# button.net
KiCad netlist of a schematic drawn in Altium Designer
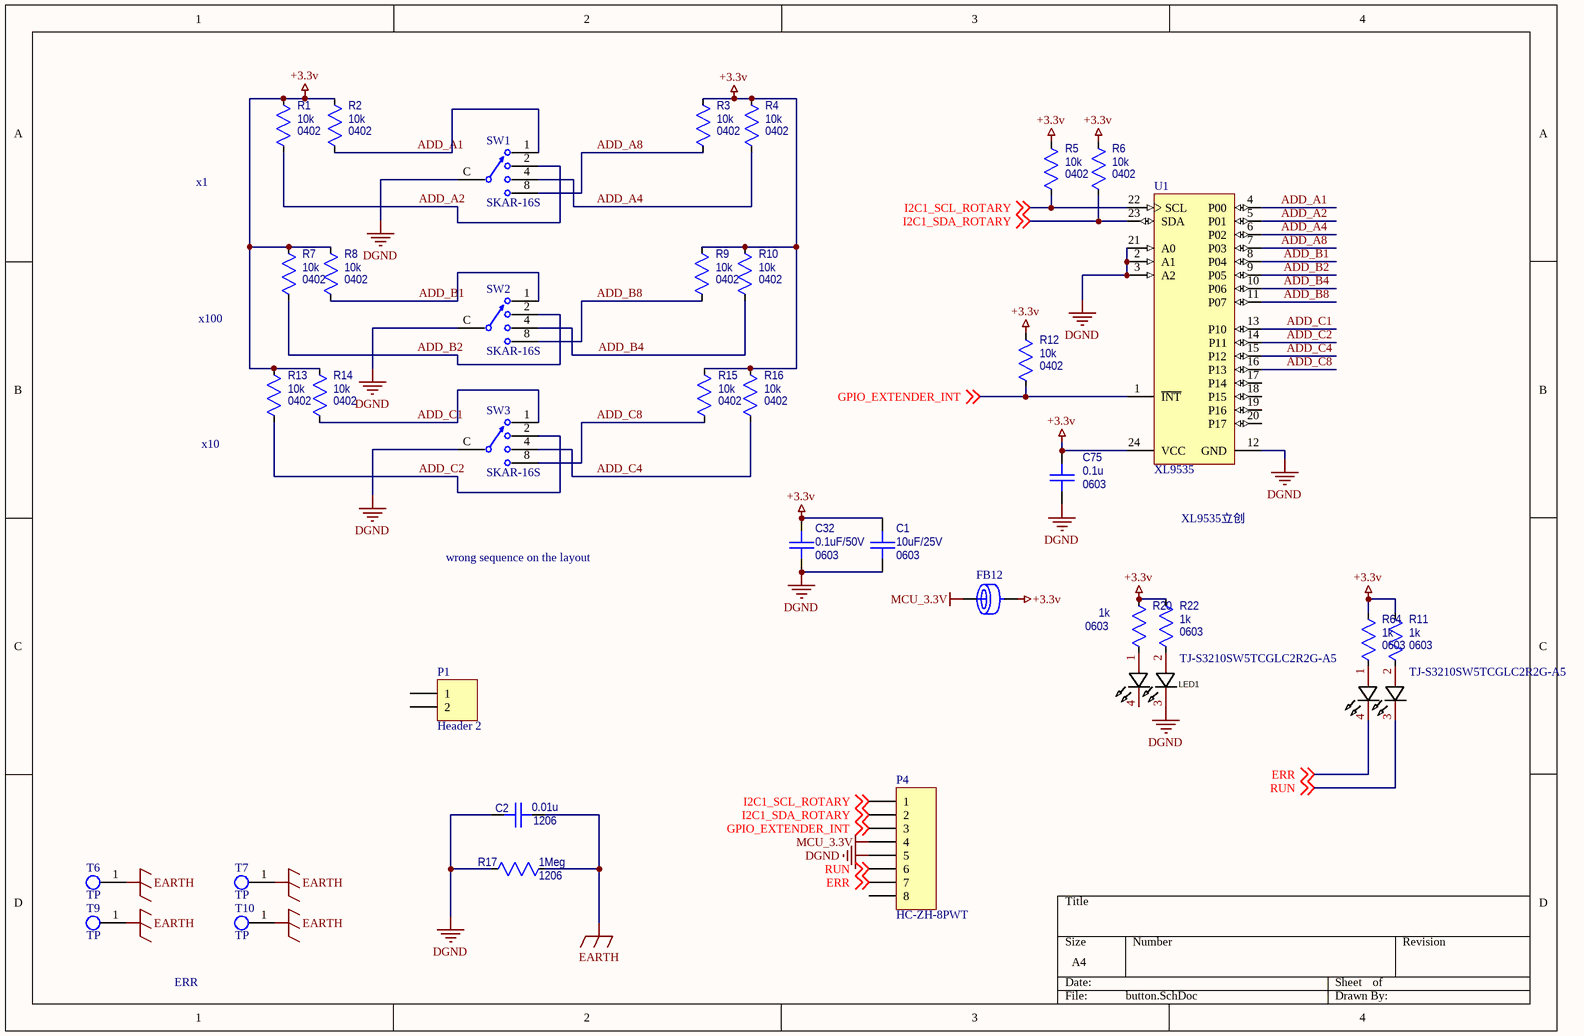
[diagram p0: button.SchDoc]

(export (version "E")
  (design (tool "Eeschema 10.0.6"))
  (components
    (comp (ref "C1")
      (value "10uF/25V")
      (footprint "CAPC1608X092N_0603")
      (fields
        (field (name "PARTNUMBER") "C0603C104M5RACTU")
        (field (name "TOLERANCE") "[tol]")
        (field (name "PACKAGE") "0603")
        (field (name "Comment") "Capacitor_0603")
      )
      (libsource (lib "Karl") (part "Capacitor_0603"))
    )
    (comp (ref "C2")
      (value "0.01u")
      (footprint "CAPC3216X156N_1206")
      (description "Capacitor, MLCC")
      (fields
        (field (name "PARTNUMBER") "C1206C103KCRACTU")
        (field (name "TOLERANCE") "[tol]")
        (field (name "PACKAGE") "1206")
      )
      (libsource (lib "Karl") (part "Capacitor_1206"))
    )
    (comp (ref "C32")
      (value "0.1uF/50V")
      (footprint "CAPC1608X092N_0603")
      (fields
        (field (name "PARTNUMBER") "C0603C104M5RACTU")
        (field (name "TOLERANCE") "[tol]")
        (field (name "PACKAGE") "0603")
        (field (name "Comment") "Capacitor_0603")
      )
      (libsource (lib "Karl") (part "Capacitor_0603"))
    )
    (comp (ref "C75")
      (value "0.1u")
      (footprint "CAPC1608X092N_0603")
      (description "Capacitor, MLCC")
      (fields
        (field (name "MANUFACTURER") "KEMET")
        (field (name "PARTNUMBER") "C0603C104M5RACTU")
        (field (name "PACKAGE") "0603")
      )
      (libsource (lib "Karl") (part "Capacitor_0603"))
    )
    (comp (ref "FB12")
      (value "FBC0603")
      (footprint "FBC0603")
      (fields (field (name "PARTNUMBER") "PE-0603PFB121ST"))
      (libsource (lib "Karl") (part "FBC0603"))
    )
    (comp (ref "LED1")
      (value "TJ-S3210SW5TCGLC2R2G-A5")
      (footprint "LED-SMD_4P-L3.2-W1.5_TJ-S3210SW5TCGLC2R2G")
      (libsource (lib "altium-import") (part "root_1_TJ-S3210SW5TCGLC2R2G-A5_"))
    )
    (comp (ref "LED2")
      (value "TJ-S3210SW5TCGLC2R2G-A5")
      (footprint "LED-SMD_4P-L3.2-W1.5_TJ-S3210SW5TCGLC2R2G")
      (libsource (lib "altium-import") (part "root_1_TJ-S3210SW5TCGLC2R2G-A5_"))
    )
    (comp (ref "P1")
      (value "Header 2")
      (footprint "HDR1X2")
      (description "Header, 2-Pin")
      (fields (field (name "PUBLISHER") "Altium Limited"))
      (libsource (lib "Miscellaneous Connectors") (part "Header 2"))
    )
    (comp (ref "P4")
      (value "HC-ZH-8PWT")
      (footprint "CONN-TH_HC-ZH1.5-8A")
      (description "Header, 8-Pin")
      (fields (field (name "PUBLISHER") "Altium Limited"))
      (libsource (lib "Miscellaneous Connectors") (part "Header 8"))
    )
    (comp (ref "R1")
      (value "10k")
      (footprint "RESC1608X055N_0603")
      (description "Resistor, Standard")
      (fields
        (field (name "MANUFACTURER") "Panasonic")
        (field (name "PARTNUMBER") "ERJ-2RKF1002X")
        (field (name "PACKAGE") "0402")
      )
      (libsource (lib "Karl") (part "Resistor_0402"))
    )
    (comp (ref "R2")
      (value "10k")
      (footprint "RESC1608X055N_0603")
      (description "Resistor, Standard")
      (fields
        (field (name "MANUFACTURER") "Panasonic")
        (field (name "PARTNUMBER") "ERJ-2RKF1002X")
        (field (name "PACKAGE") "0402")
      )
      (libsource (lib "Karl") (part "Resistor_0402"))
    )
    (comp (ref "R3")
      (value "10k")
      (footprint "RESC1608X055N_0603")
      (description "Resistor, Standard")
      (fields
        (field (name "MANUFACTURER") "Panasonic")
        (field (name "PARTNUMBER") "ERJ-2RKF1002X")
        (field (name "PACKAGE") "0402")
      )
      (libsource (lib "Karl") (part "Resistor_0402"))
    )
    (comp (ref "R4")
      (value "10k")
      (footprint "RESC1608X055N_0603")
      (description "Resistor, Standard")
      (fields
        (field (name "MANUFACTURER") "Panasonic")
        (field (name "PARTNUMBER") "ERJ-2RKF1002X")
        (field (name "PACKAGE") "0402")
      )
      (libsource (lib "Karl") (part "Resistor_0402"))
    )
    (comp (ref "R5")
      (value "10k")
      (footprint "RESC1608X055N_0603")
      (description "Resistor, Standard")
      (fields
        (field (name "MANUFACTURER") "Panasonic")
        (field (name "PARTNUMBER") "ERJ-2RKF1002X")
        (field (name "PACKAGE") "0402")
      )
      (libsource (lib "Karl") (part "Resistor_0402"))
    )
    (comp (ref "R6")
      (value "10k")
      (footprint "RESC1608X055N_0603")
      (description "Resistor, Standard")
      (fields
        (field (name "MANUFACTURER") "Panasonic")
        (field (name "PARTNUMBER") "ERJ-2RKF1002X")
        (field (name "PACKAGE") "0402")
      )
      (libsource (lib "Karl") (part "Resistor_0402"))
    )
    (comp (ref "R7")
      (value "10k")
      (footprint "RESC1608X055N_0603")
      (description "Resistor, Standard")
      (fields
        (field (name "MANUFACTURER") "Panasonic")
        (field (name "PARTNUMBER") "ERJ-2RKF1002X")
        (field (name "PACKAGE") "0402")
      )
      (libsource (lib "Karl") (part "Resistor_0402"))
    )
    (comp (ref "R8")
      (value "10k")
      (footprint "RESC1608X055N_0603")
      (description "Resistor, Standard")
      (fields
        (field (name "MANUFACTURER") "Panasonic")
        (field (name "PARTNUMBER") "ERJ-2RKF1002X")
        (field (name "PACKAGE") "0402")
      )
      (libsource (lib "Karl") (part "Resistor_0402"))
    )
    (comp (ref "R9")
      (value "10k")
      (footprint "RESC1608X055N_0603")
      (description "Resistor, Standard")
      (fields
        (field (name "MANUFACTURER") "Panasonic")
        (field (name "PARTNUMBER") "ERJ-2RKF1002X")
        (field (name "PACKAGE") "0402")
      )
      (libsource (lib "Karl") (part "Resistor_0402"))
    )
    (comp (ref "R10")
      (value "10k")
      (footprint "RESC1608X055N_0603")
      (description "Resistor, Standard")
      (fields
        (field (name "MANUFACTURER") "Panasonic")
        (field (name "PARTNUMBER") "ERJ-2RKF1002X")
        (field (name "PACKAGE") "0402")
      )
      (libsource (lib "Karl") (part "Resistor_0402"))
    )
    (comp (ref "R11")
      (value "1k")
      (footprint "RESC1608X055N_0603")
      (description "Resistor, Standard")
      (fields
        (field (name "MANUFACTURER") "Yageo")
        (field (name "PARTNUMBER") "RC0603FR-071KL")
        (field (name "PACKAGE") "0603")
      )
      (libsource (lib "Karl") (part "Resistor_0603"))
    )
    (comp (ref "R12")
      (value "10k")
      (footprint "RESC1608X055N_0603")
      (description "Resistor, Standard")
      (fields
        (field (name "MANUFACTURER") "Panasonic")
        (field (name "PARTNUMBER") "ERJ-2RKF1002X")
        (field (name "PACKAGE") "0402")
      )
      (libsource (lib "Karl") (part "Resistor_0402"))
    )
    (comp (ref "R13")
      (value "10k")
      (footprint "RESC1608X055N_0603")
      (description "Resistor, Standard")
      (fields
        (field (name "MANUFACTURER") "Panasonic")
        (field (name "PARTNUMBER") "ERJ-2RKF1002X")
        (field (name "PACKAGE") "0402")
      )
      (libsource (lib "Karl") (part "Resistor_0402"))
    )
    (comp (ref "R14")
      (value "10k")
      (footprint "RESC1608X055N_0603")
      (description "Resistor, Standard")
      (fields
        (field (name "MANUFACTURER") "Panasonic")
        (field (name "PARTNUMBER") "ERJ-2RKF1002X")
        (field (name "PACKAGE") "0402")
      )
      (libsource (lib "Karl") (part "Resistor_0402"))
    )
    (comp (ref "R15")
      (value "10k")
      (footprint "RESC1608X055N_0603")
      (description "Resistor, Standard")
      (fields
        (field (name "MANUFACTURER") "Panasonic")
        (field (name "PARTNUMBER") "ERJ-2RKF1002X")
        (field (name "PACKAGE") "0402")
      )
      (libsource (lib "Karl") (part "Resistor_0402"))
    )
    (comp (ref "R16")
      (value "10k")
      (footprint "RESC1608X055N_0603")
      (description "Resistor, Standard")
      (fields
        (field (name "MANUFACTURER") "Panasonic")
        (field (name "PARTNUMBER") "ERJ-2RKF1002X")
        (field (name "PACKAGE") "0402")
      )
      (libsource (lib "Karl") (part "Resistor_0402"))
    )
    (comp (ref "R17")
      (value "1Meg")
      (footprint "RESC3216X070N_1206")
      (description "Resistor, Standard")
      (fields
        (field (name "PARTNUMBER") "RC1206FR-071ML")
        (field (name "TOLERANCE") "tol")
        (field (name "PACKAGE") "1206")
      )
      (libsource (lib "Karl") (part "Resistor_1206"))
    )
    (comp (ref "R20")
      (value "1k")
      (footprint "RESC1608X055N_0603")
      (description "Resistor, Standard")
      (fields
        (field (name "MANUFACTURER") "Yageo")
        (field (name "PARTNUMBER") "RC0603FR-071KL")
        (field (name "PACKAGE") "0603")
      )
      (libsource (lib "Karl") (part "Resistor_0603"))
    )
    (comp (ref "R22")
      (value "1k")
      (footprint "RESC1608X055N_0603")
      (description "Resistor, Standard")
      (fields
        (field (name "MANUFACTURER") "Yageo")
        (field (name "PARTNUMBER") "RC0603FR-071KL")
        (field (name "PACKAGE") "0603")
      )
      (libsource (lib "Karl") (part "Resistor_0603"))
    )
    (comp (ref "R64")
      (value "1k")
      (footprint "RESC1608X055N_0603")
      (description "Resistor, Standard")
      (fields
        (field (name "MANUFACTURER") "Yageo")
        (field (name "PARTNUMBER") "RC0603FR-071KL")
        (field (name "PACKAGE") "0603")
      )
      (libsource (lib "Karl") (part "Resistor_0603"))
    )
    (comp (ref "SW1")
      (value "SKAR-16S")
      (footprint "SW-SMD_SM_STAR-10S")
      (description "Mini Rotary DIP Switch, 16 Postions, Right Angle Thru-Hole, -60 to 125 degC, 6-Pin THT, RoHS")
      (fields (field (name "PART NO") "MSDR-16H1") (field (name "MANUFACTURER") "SUNGMUN ELECTRONICS"))
      (libsource (lib "Bogen") (part "MSDR-16H1"))
    )
    (comp (ref "SW2")
      (value "SKAR-16S")
      (footprint "SW-SMD_SM_STAR-10S")
      (description "Mini Rotary DIP Switch, 16 Postions, Right Angle Thru-Hole, -60 to 125 degC, 6-Pin THT, RoHS")
      (fields (field (name "PART NO") "MSDR-16H1") (field (name "MANUFACTURER") "SUNGMUN ELECTRONICS"))
      (libsource (lib "Bogen") (part "MSDR-16H1"))
    )
    (comp (ref "SW3")
      (value "SKAR-16S")
      (footprint "SW-SMD_SM_STAR-10S")
      (description "Mini Rotary DIP Switch, 16 Postions, Right Angle Thru-Hole, -60 to 125 degC, 6-Pin THT, RoHS")
      (fields (field (name "PART NO") "MSDR-16H1") (field (name "MANUFACTURER") "SUNGMUN ELECTRONICS"))
      (libsource (lib "Bogen") (part "MSDR-16H1"))
    )
    (comp (ref "T6") (value "TP") (footprint "FIX-2.5") (libsource (lib "Schlib_20110825") (part "TP")))
    (comp (ref "T7") (value "TP") (footprint "FIX-2.5") (libsource (lib "Schlib_20110825") (part "TP")))
    (comp (ref "T9") (value "TP") (footprint "FIX-2.5") (libsource (lib "Schlib_20110825") (part "TP")))
    (comp (ref "T10") (value "TP") (footprint "FIX-2.5") (libsource (lib "Schlib_20110825") (part "TP")))
    (comp (ref "U1")
      (value "XL9535")
      (footprint "XNLD-TSSOP24_N")
      (fields (field (name "MANUFACTURER") "XINLUDA"))
      (libsource (lib "Bogen") (part "XL9535"))
    )
  )
  (nets
    (net (code "1") (name "+3.3v") (class "Default")
      (node (ref "C1") (pin "1") (pinfunction "1_1") (pintype "passive"))
      (node (ref "C32") (pin "1") (pinfunction "1_1") (pintype "passive"))
      (node (ref "C75") (pin "1") (pinfunction "1_1") (pintype "passive"))
      (node (ref "FB12") (pin "2") (pinfunction "2_2") (pintype "passive"))
      (node (ref "R1") (pin "2") (pinfunction "2_2") (pintype "passive"))
      (node (ref "R10") (pin "2") (pinfunction "2_2") (pintype "passive"))
      (node (ref "R11") (pin "2") (pinfunction "2_2") (pintype "passive"))
      (node (ref "R12") (pin "2") (pinfunction "2_2") (pintype "passive"))
      (node (ref "R13") (pin "2") (pinfunction "2_2") (pintype "passive"))
      (node (ref "R14") (pin "2") (pinfunction "2_2") (pintype "passive"))
      (node (ref "R15") (pin "2") (pinfunction "2_2") (pintype "passive"))
      (node (ref "R16") (pin "2") (pinfunction "2_2") (pintype "passive"))
      (node (ref "R2") (pin "2") (pinfunction "2_2") (pintype "passive"))
      (node (ref "R20") (pin "2") (pinfunction "2_2") (pintype "passive"))
      (node (ref "R22") (pin "2") (pinfunction "2_2") (pintype "passive"))
      (node (ref "R3") (pin "2") (pinfunction "2_2") (pintype "passive"))
      (node (ref "R4") (pin "2") (pinfunction "2_2") (pintype "passive"))
      (node (ref "R5") (pin "2") (pinfunction "2_2") (pintype "passive"))
      (node (ref "R6") (pin "2") (pinfunction "2_2") (pintype "passive"))
      (node (ref "R64") (pin "2") (pinfunction "2_2") (pintype "passive"))
      (node (ref "R7") (pin "2") (pinfunction "2_2") (pintype "passive"))
      (node (ref "R8") (pin "2") (pinfunction "2_2") (pintype "passive"))
      (node (ref "R9") (pin "2") (pinfunction "2_2") (pintype "passive"))
      (node (ref "U1") (pin "24") (pinfunction "VCC_24") (pintype "power_in"))
    )
    (net (code "2") (name "/ADD_A1") (class "Default")
      (node (ref "R2") (pin "1") (pinfunction "1_1") (pintype "passive"))
      (node (ref "SW1") (pin "1") (pinfunction "1_1") (pintype "passive"))
      (node (ref "U1") (pin "4") (pinfunction "P00_4") (pintype "bidirectional"))
    )
    (net (code "3") (name "/ADD_A2") (class "Default")
      (node (ref "R1") (pin "1") (pinfunction "1_1") (pintype "passive"))
      (node (ref "SW1") (pin "2") (pinfunction "2_2") (pintype "passive"))
      (node (ref "U1") (pin "5") (pinfunction "P01_5") (pintype "bidirectional"))
    )
    (net (code "4") (name "/ADD_A4") (class "Default")
      (node (ref "R4") (pin "1") (pinfunction "1_1") (pintype "passive"))
      (node (ref "SW1") (pin "4") (pinfunction "4_4") (pintype "passive"))
      (node (ref "U1") (pin "6") (pinfunction "P02_6") (pintype "bidirectional"))
    )
    (net (code "5") (name "/ADD_A8") (class "Default")
      (node (ref "R3") (pin "1") (pinfunction "1_1") (pintype "passive"))
      (node (ref "SW1") (pin "8") (pinfunction "8_8") (pintype "passive"))
      (node (ref "U1") (pin "7") (pinfunction "P03_7") (pintype "bidirectional"))
    )
    (net (code "6") (name "/ADD_B1") (class "Default")
      (node (ref "R8") (pin "1") (pinfunction "1_1") (pintype "passive"))
      (node (ref "SW2") (pin "1") (pinfunction "1_1") (pintype "passive"))
      (node (ref "U1") (pin "8") (pinfunction "P04_8") (pintype "bidirectional"))
    )
    (net (code "7") (name "/ADD_B2") (class "Default")
      (node (ref "R7") (pin "1") (pinfunction "1_1") (pintype "passive"))
      (node (ref "SW2") (pin "2") (pinfunction "2_2") (pintype "passive"))
      (node (ref "U1") (pin "9") (pinfunction "P05_9") (pintype "bidirectional"))
    )
    (net (code "8") (name "/ADD_B4") (class "Default")
      (node (ref "R10") (pin "1") (pinfunction "1_1") (pintype "passive"))
      (node (ref "SW2") (pin "4") (pinfunction "4_4") (pintype "passive"))
      (node (ref "U1") (pin "10") (pinfunction "P06_10") (pintype "bidirectional"))
    )
    (net (code "9") (name "/ADD_B8") (class "Default")
      (node (ref "R9") (pin "1") (pinfunction "1_1") (pintype "passive"))
      (node (ref "SW2") (pin "8") (pinfunction "8_8") (pintype "passive"))
      (node (ref "U1") (pin "11") (pinfunction "P07_11") (pintype "bidirectional"))
    )
    (net (code "10") (name "/ADD_C1") (class "Default")
      (node (ref "R14") (pin "1") (pinfunction "1_1") (pintype "passive"))
      (node (ref "SW3") (pin "1") (pinfunction "1_1") (pintype "passive"))
      (node (ref "U1") (pin "13") (pinfunction "P10_13") (pintype "bidirectional"))
    )
    (net (code "11") (name "/ADD_C2") (class "Default")
      (node (ref "R13") (pin "1") (pinfunction "1_1") (pintype "passive"))
      (node (ref "SW3") (pin "2") (pinfunction "2_2") (pintype "passive"))
      (node (ref "U1") (pin "14") (pinfunction "P11_14") (pintype "bidirectional"))
    )
    (net (code "12") (name "/ADD_C4") (class "Default")
      (node (ref "R16") (pin "1") (pinfunction "1_1") (pintype "passive"))
      (node (ref "SW3") (pin "4") (pinfunction "4_4") (pintype "passive"))
      (node (ref "U1") (pin "15") (pinfunction "P12_15") (pintype "bidirectional"))
    )
    (net (code "13") (name "/ADD_C8") (class "Default")
      (node (ref "R15") (pin "1") (pinfunction "1_1") (pintype "passive"))
      (node (ref "SW3") (pin "8") (pinfunction "8_8") (pintype "passive"))
      (node (ref "U1") (pin "16") (pinfunction "P13_16") (pintype "bidirectional"))
    )
    (net (code "14") (name "DGND") (class "Default")
      (node (ref "C1") (pin "2") (pinfunction "2_2") (pintype "passive"))
      (node (ref "C2") (pin "1") (pinfunction "1_1") (pintype "passive"))
      (node (ref "C32") (pin "2") (pinfunction "2_2") (pintype "passive"))
      (node (ref "C75") (pin "2") (pinfunction "2_2") (pintype "passive"))
      (node (ref "LED1") (pin "3") (pinfunction "-_3") (pintype "passive"))
      (node (ref "P4") (pin "5") (pinfunction "5_5") (pintype "passive"))
      (node (ref "R17") (pin "2") (pinfunction "2_2") (pintype "passive"))
      (node (ref "SW1") (pin "C") (pinfunction "C_C") (pintype "passive"))
      (node (ref "SW2") (pin "C") (pinfunction "C_C") (pintype "passive"))
      (node (ref "SW3") (pin "C") (pinfunction "C_C") (pintype "passive"))
      (node (ref "U1") (pin "12") (pinfunction "GND_12") (pintype "power_in"))
      (node (ref "U1") (pin "2") (pinfunction "A1_2") (pintype "input"))
      (node (ref "U1") (pin "21") (pinfunction "A0_21") (pintype "input"))
      (node (ref "U1") (pin "3") (pinfunction "A2_3") (pintype "input"))
    )
    (net (code "15") (name "EARTH") (class "Default")
      (node (ref "C2") (pin "2") (pinfunction "2_2") (pintype "passive"))
      (node (ref "R17") (pin "1") (pinfunction "1_1") (pintype "passive"))
      (node (ref "T10") (pin "1") (pintype "passive"))
      (node (ref "T6") (pin "1") (pintype "passive"))
      (node (ref "T7") (pin "1") (pintype "passive"))
      (node (ref "T9") (pin "1") (pintype "passive"))
    )
    (net (code "16") (name "ERR") (class "Default")
      (node (ref "LED2") (pin "4") (pinfunction "-_4") (pintype "passive"))
      (node (ref "P4") (pin "7") (pinfunction "7_7") (pintype "passive"))
    )
    (net (code "17") (name "GPIO_EXTENDER_INT") (class "Default")
      (node (ref "P4") (pin "3") (pinfunction "3_3") (pintype "passive"))
      (node (ref "R12") (pin "1") (pinfunction "1_1") (pintype "passive"))
      (node (ref "U1") (pin "1") (pinfunction "~{INT}_1") (pintype "open_collector"))
    )
    (net (code "18") (name "I2C1_SCL_ROTARY") (class "Default")
      (node (ref "P4") (pin "1") (pinfunction "1_1") (pintype "passive"))
      (node (ref "R5") (pin "1") (pinfunction "1_1") (pintype "passive"))
      (node (ref "U1") (pin "22") (pinfunction "SCL_22") (pintype "input"))
    )
    (net (code "19") (name "I2C1_SDA_ROTARY") (class "Default")
      (node (ref "P4") (pin "2") (pinfunction "2_2") (pintype "passive"))
      (node (ref "R6") (pin "1") (pinfunction "1_1") (pintype "passive"))
      (node (ref "U1") (pin "23") (pinfunction "SDA_23") (pintype "bidirectional"))
    )
    (net (code "20") (name "MCU_3.3V") (class "Default")
      (node (ref "FB12") (pin "1") (pinfunction "1_1") (pintype "passive"))
      (node (ref "P4") (pin "4") (pinfunction "4_4") (pintype "passive"))
    )
    (net (code "21") (name "Net-(LED1-+-Pad1)") (class "Default")
      (node (ref "LED1") (pin "1") (pinfunction "+_1") (pintype "passive"))
      (node (ref "R20") (pin "1") (pinfunction "1_1") (pintype "passive"))
    )
    (net (code "22") (name "Net-(LED1-+-Pad2)") (class "Default")
      (node (ref "LED1") (pin "2") (pinfunction "+_2") (pintype "passive"))
      (node (ref "R22") (pin "1") (pinfunction "1_1") (pintype "passive"))
    )
    (net (code "23") (name "Net-(LED2-+-Pad1)") (class "Default")
      (node (ref "LED2") (pin "1") (pinfunction "+_1") (pintype "passive"))
      (node (ref "R64") (pin "1") (pinfunction "1_1") (pintype "passive"))
    )
    (net (code "24") (name "Net-(LED2-+-Pad2)") (class "Default")
      (node (ref "LED2") (pin "2") (pinfunction "+_2") (pintype "passive"))
      (node (ref "R11") (pin "1") (pinfunction "1_1") (pintype "passive"))
    )
    (net (code "25") (name "RUN") (class "Default")
      (node (ref "LED2") (pin "3") (pinfunction "-_3") (pintype "passive"))
      (node (ref "P4") (pin "6") (pinfunction "6_6") (pintype "passive"))
    )
    (net (code "26") (name "unconnected-(LED1---Pad4)") (class "Default")
      (node (ref "LED1") (pin "4") (pinfunction "-_4") (pintype "passive"))
    )
    (net (code "27") (name "unconnected-(P1-Pad1)") (class "Default")
      (node (ref "P1") (pin "1") (pinfunction "1_1") (pintype "passive"))
    )
    (net (code "28") (name "unconnected-(P1-Pad2)") (class "Default")
      (node (ref "P1") (pin "2") (pinfunction "2_2") (pintype "passive"))
    )
    (net (code "29") (name "unconnected-(P4-Pad8)") (class "Default")
      (node (ref "P4") (pin "8") (pinfunction "8_8") (pintype "passive"))
    )
    (net (code "30") (name "unconnected-(U1-P14-Pad17)") (class "Default")
      (node (ref "U1") (pin "17") (pinfunction "P14_17") (pintype "bidirectional"))
    )
    (net (code "31") (name "unconnected-(U1-P15-Pad18)") (class "Default")
      (node (ref "U1") (pin "18") (pinfunction "P15_18") (pintype "bidirectional"))
    )
    (net (code "32") (name "unconnected-(U1-P16-Pad19)") (class "Default")
      (node (ref "U1") (pin "19") (pinfunction "P16_19") (pintype "bidirectional"))
    )
    (net (code "33") (name "unconnected-(U1-P17-Pad20)") (class "Default")
      (node (ref "U1") (pin "20") (pinfunction "P17_20") (pintype "bidirectional"))
    )
  )
)
